# fans.net
KiCad netlist of a schematic drawn in Altium Designer
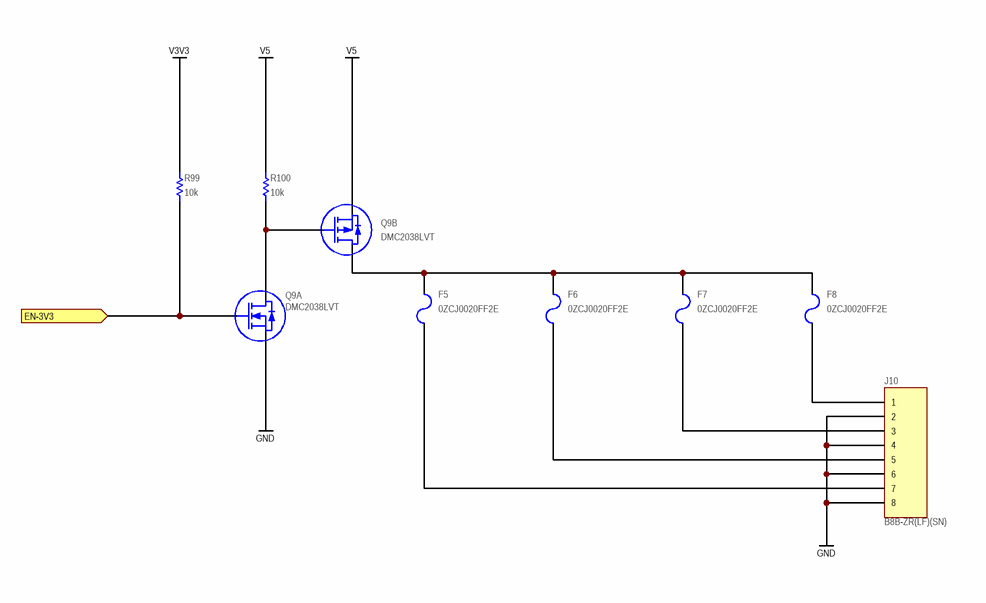
[diagram p0: fans.SchDoc]

(export (version "E")
  (design (tool "Eeschema 10.0.6"))
  (components
    (comp (ref "F5")
      (value "0ZCJ0020FF2E")
      (footprint "generic:1206")
      (description "PTC Resettable Fuse, 0.2A, 30V, SMD 1206")
      (fields (field (name "MANUFACTURER") "Bell Fuse"))
      (libsource (lib "bel-fuse") (part "0ZCJ0020FF2E"))
    )
    (comp (ref "F6")
      (value "0ZCJ0020FF2E")
      (footprint "generic:1206")
      (description "PTC Resettable Fuse, 0.2A, 30V, SMD 1206")
      (fields (field (name "MANUFACTURER") "Bell Fuse"))
      (libsource (lib "bel-fuse") (part "0ZCJ0020FF2E"))
    )
    (comp (ref "F7")
      (value "0ZCJ0020FF2E")
      (footprint "generic:1206")
      (description "PTC Resettable Fuse, 0.2A, 30V, SMD 1206")
      (fields (field (name "MANUFACTURER") "Bell Fuse"))
      (libsource (lib "bel-fuse") (part "0ZCJ0020FF2E"))
    )
    (comp (ref "F8")
      (value "0ZCJ0020FF2E")
      (footprint "generic:1206")
      (description "PTC Resettable Fuse, 0.2A, 30V, SMD 1206")
      (fields (field (name "MANUFACTURER") "Bell Fuse"))
      (libsource (lib "bel-fuse") (part "0ZCJ0020FF2E"))
    )
    (comp (ref "J10")
      (value "B8B-ZR(LF)(SN)")
      (footprint "jst:B8B-ZR")
      (description "Through-hole Shrouded Header 8-Position")
      (fields (field (name "MANUFACTURER") "JST"))
      (libsource (lib "Miscellaneous Connectors") (part "Header 8"))
    )
    (comp (ref "Q9")
      (value "DMC2038LVT")
      (footprint "generic:TSOP-6")
      (description "Complementary MOSFET Pair")
      (fields (field (name "MANUFACTURER") "Diodes, Inc."))
      (libsource (lib "") (part "DMC2038LVT_1"))
    )
    (comp (ref "R99")
      (value "10k")
      (footprint "RESC1005X40N")
      (description "Thick Film Resistor 10k ±1% 0.1W 50V 0402")
      (fields (field (name "MANUFACTURER") "Panasonic") (field (name "TOLERANCE") "±1%"))
      (libsource (lib "generic") (part "RES"))
    )
    (comp (ref "R100")
      (value "10k")
      (footprint "RESC1005X40N")
      (description "Thick Film Resistor 10k ±1% 0.1W 50V 0402")
      (fields (field (name "MANUFACTURER") "Panasonic") (field (name "TOLERANCE") "±1%"))
      (libsource (lib "generic") (part "RES"))
    )
  )
  (nets
    (net (code "1") (name "/EN-3V3") (class "Default")
      (node (ref "Q9") (pin "1") (pinfunction "G_1") (pintype "passive"))
      (node (ref "R99") (pin "1") (pinfunction "1_1") (pintype "passive"))
    )
    (net (code "2") (name "GND") (class "Default")
      (node (ref "J10") (pin "2") (pinfunction "2_2") (pintype "passive"))
      (node (ref "J10") (pin "4") (pinfunction "4_4") (pintype "passive"))
      (node (ref "J10") (pin "6") (pinfunction "6_6") (pintype "passive"))
      (node (ref "J10") (pin "8") (pinfunction "8_8") (pintype "passive"))
      (node (ref "Q9") (pin "5") (pinfunction "S_5") (pintype "passive"))
    )
    (net (code "3") (name "Net-(F5-Pad2)") (class "Default")
      (node (ref "F5") (pin "2") (pinfunction "2_2") (pintype "passive"))
      (node (ref "J10") (pin "7") (pinfunction "7_7") (pintype "passive"))
    )
    (net (code "4") (name "Net-(F6-Pad2)") (class "Default")
      (node (ref "F6") (pin "2") (pinfunction "2_2") (pintype "passive"))
      (node (ref "J10") (pin "5") (pinfunction "5_5") (pintype "passive"))
    )
    (net (code "5") (name "Net-(F7-Pad2)") (class "Default")
      (node (ref "F7") (pin "2") (pinfunction "2_2") (pintype "passive"))
      (node (ref "J10") (pin "3") (pinfunction "3_3") (pintype "passive"))
    )
    (net (code "6") (name "Net-(F8-Pad2)") (class "Default")
      (node (ref "F8") (pin "2") (pinfunction "2_2") (pintype "passive"))
      (node (ref "J10") (pin "1") (pinfunction "1_1") (pintype "passive"))
    )
    (net (code "7") (name "Net-(Q9A-D)") (class "Default")
      (node (ref "Q9") (pin "3") (pinfunction "G_3") (pintype "passive"))
      (node (ref "Q9") (pin "6") (pinfunction "D_6") (pintype "passive"))
      (node (ref "R100") (pin "1") (pinfunction "1_1") (pintype "passive"))
    )
    (net (code "8") (name "Net-(Q9B-D)") (class "Default")
      (node (ref "F5") (pin "1") (pinfunction "1_1") (pintype "passive"))
      (node (ref "F6") (pin "1") (pinfunction "1_1") (pintype "passive"))
      (node (ref "F7") (pin "1") (pinfunction "1_1") (pintype "passive"))
      (node (ref "F8") (pin "1") (pinfunction "1_1") (pintype "passive"))
      (node (ref "Q9") (pin "4") (pinfunction "D_4") (pintype "passive"))
    )
    (net (code "9") (name "V3V3") (class "Default")
      (node (ref "R99") (pin "2") (pinfunction "2_2") (pintype "passive"))
    )
    (net (code "10") (name "V5") (class "Default")
      (node (ref "Q9") (pin "2") (pinfunction "S_2") (pintype "passive"))
      (node (ref "R100") (pin "2") (pinfunction "2_2") (pintype "passive"))
    )
  )
)
